# WIFI_BLE.net
KiCad netlist of a schematic drawn in Altium Designer
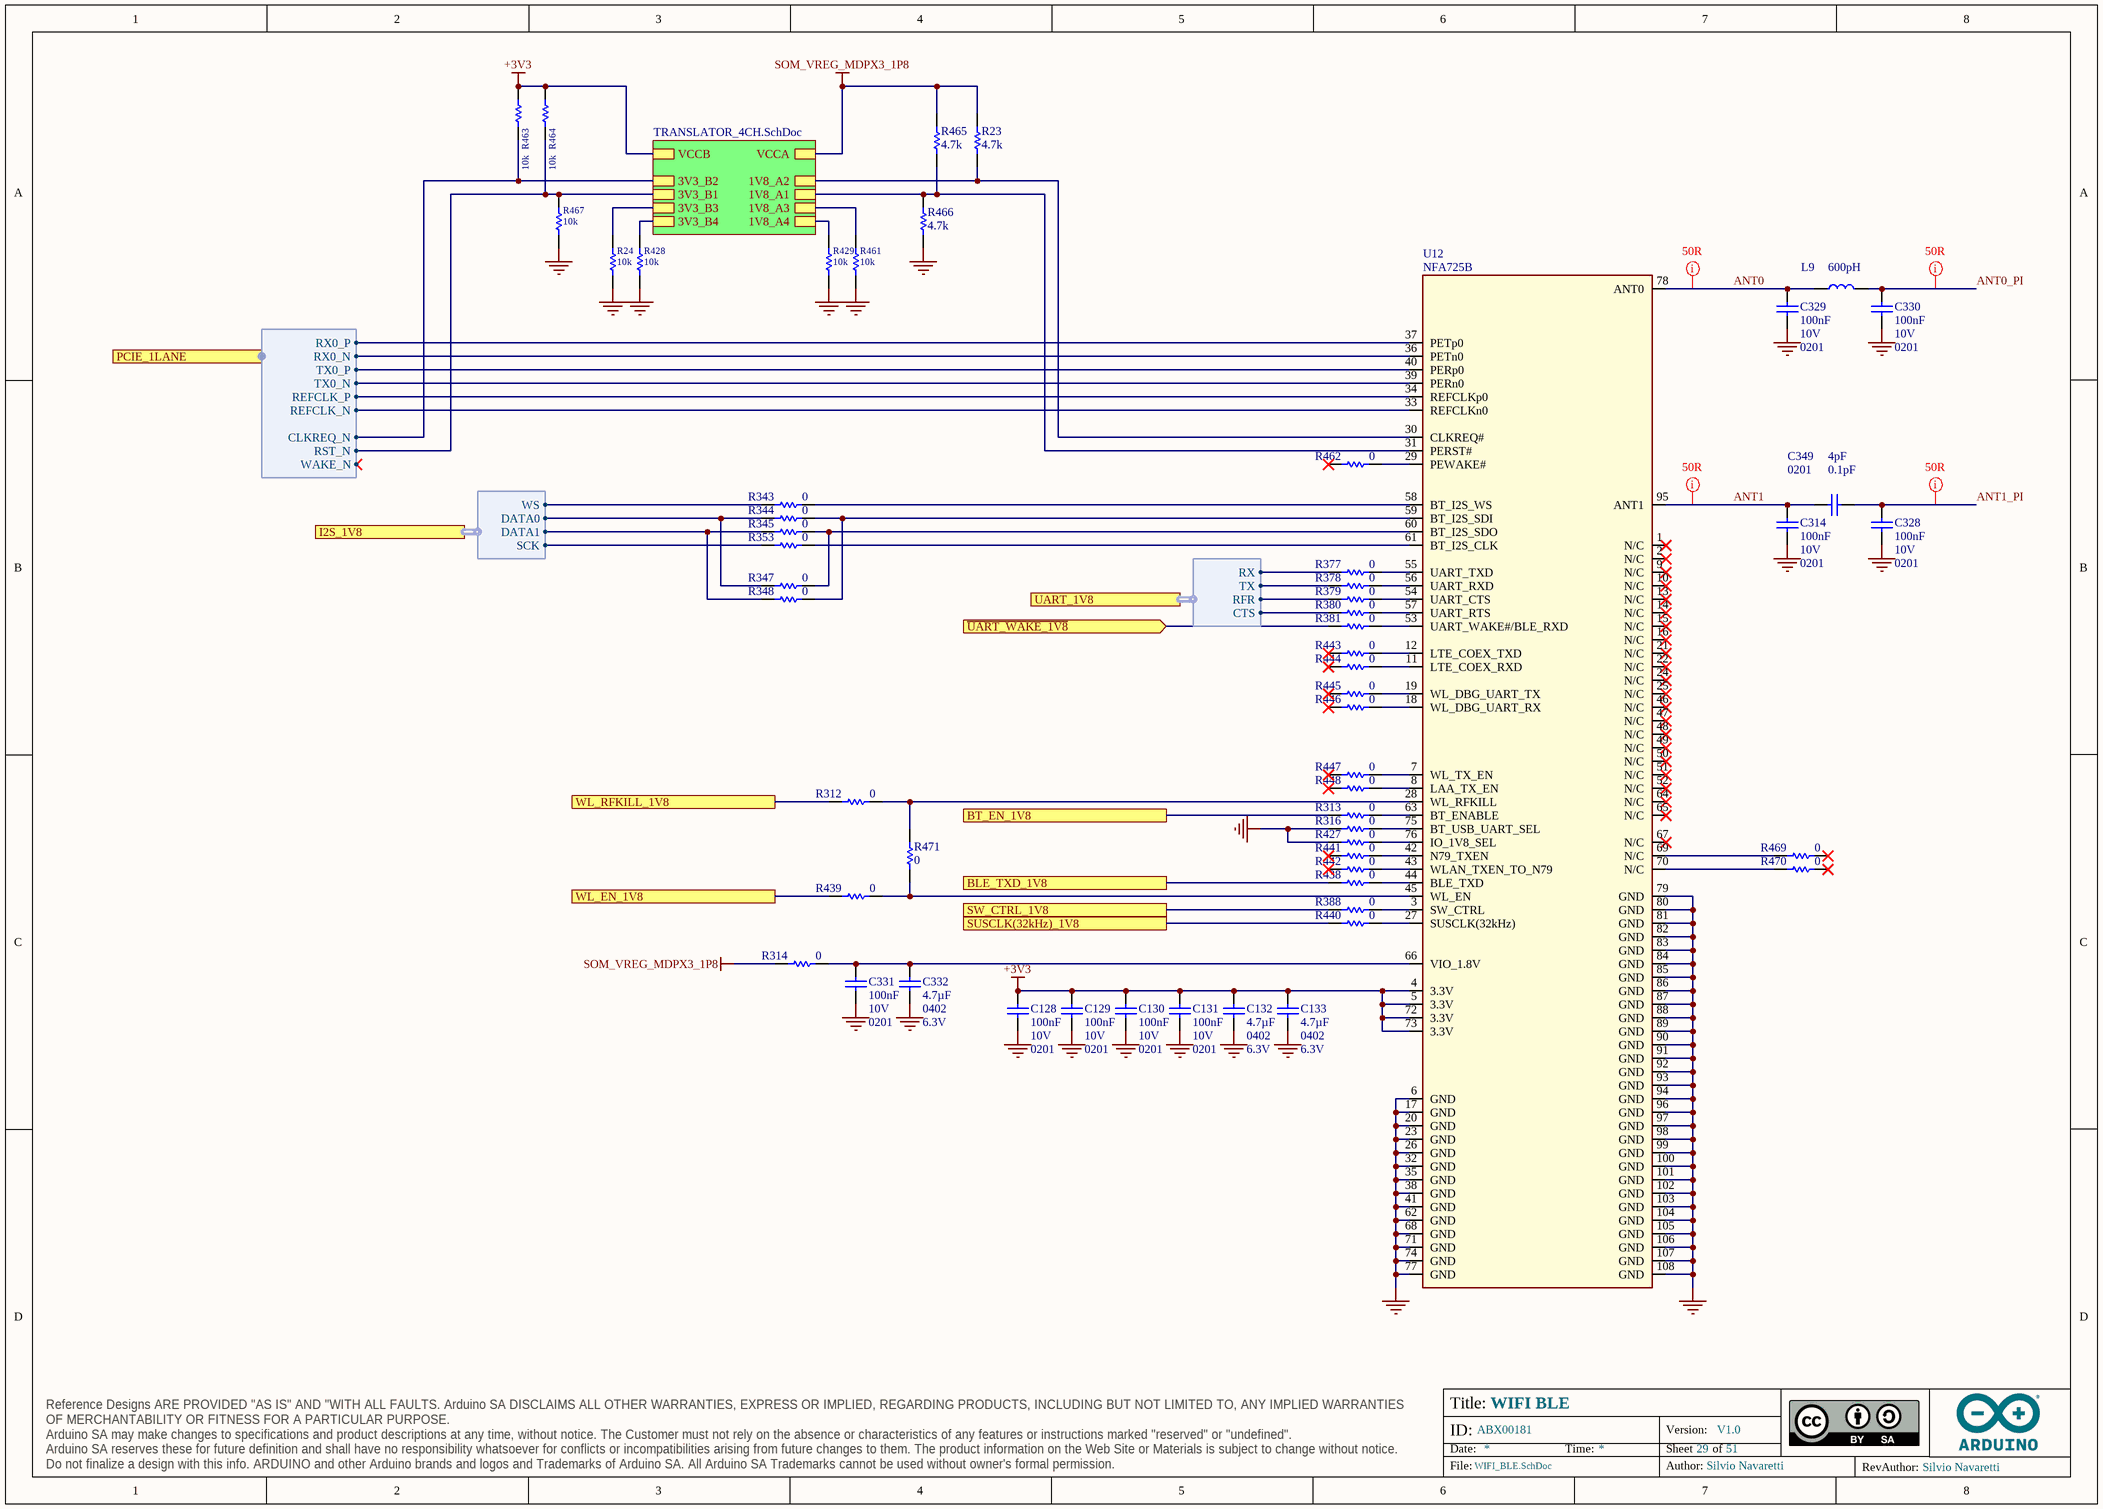
[diagram p0: WIFI_BLE.SchDoc]

(export (version "E")
  (design (tool "Eeschema 10.0.6"))
  (components
    (comp (ref "C128")
      (value "100nF")
      (footprint "CAP-0201")
      (description "CAP CHIP 0201 100nF 10% 10V X5R")
      (fields
        (field (name "PART NUMBER") "CL03A104KP3NNNC")
        (field (name "MANUFACTURER") "Samsung Electro-Mechanics")
        (field (name "VOLTAGE") "10V")
        (field (name "CASE CODE (IMPERIAL)") "0201")
      )
      (libsource (lib "Clean") (part "CAP"))
    )
    (comp (ref "C129")
      (value "100nF")
      (footprint "CAP-0201")
      (description "CAP CHIP 0201 100nF 10% 10V X5R")
      (fields
        (field (name "PART NUMBER") "CL03A104KP3NNNC")
        (field (name "MANUFACTURER") "Samsung Electro-Mechanics")
        (field (name "VOLTAGE") "10V")
        (field (name "CASE CODE (IMPERIAL)") "0201")
      )
      (libsource (lib "Clean") (part "CAP"))
    )
    (comp (ref "C130")
      (value "100nF")
      (footprint "CAP-0201")
      (description "CAP CHIP 0201 100nF 10% 10V X5R")
      (fields
        (field (name "PART NUMBER") "CL03A104KP3NNNC")
        (field (name "MANUFACTURER") "Samsung Electro-Mechanics")
        (field (name "VOLTAGE") "10V")
        (field (name "CASE CODE (IMPERIAL)") "0201")
      )
      (libsource (lib "Clean") (part "CAP"))
    )
    (comp (ref "C131")
      (value "100nF")
      (footprint "CAP-0201")
      (description "CAP CHIP 0201 100nF 10% 10V X5R")
      (fields
        (field (name "PART NUMBER") "CL03A104KP3NNNC")
        (field (name "MANUFACTURER") "Samsung Electro-Mechanics")
        (field (name "VOLTAGE") "10V")
        (field (name "CASE CODE (IMPERIAL)") "0201")
      )
      (libsource (lib "Clean") (part "CAP"))
    )
    (comp (ref "C132")
      (value "4.7µF")
      (footprint "CAP-0402")
      (description "CAP CHIP 0402 4.7uF 20% 6V3 X5R")
      (fields
        (field (name "MANUFACTURER") "Hottech")
        (field (name "PART NUMBER") "C1005A475M6R3NT")
        (field (name "CASE CODE (IMPERIAL)") "0402")
        (field (name "VOLTAGE") "6.3V")
      )
      (libsource (lib "Clean") (part "CAP"))
    )
    (comp (ref "C133")
      (value "4.7µF")
      (footprint "CAP-0402")
      (description "CAP CHIP 0402 4.7uF 20% 6V3 X5R")
      (fields
        (field (name "MANUFACTURER") "Hottech")
        (field (name "PART NUMBER") "C1005A475M6R3NT")
        (field (name "CASE CODE (IMPERIAL)") "0402")
        (field (name "VOLTAGE") "6.3V")
      )
      (libsource (lib "Clean") (part "CAP"))
    )
    (comp (ref "C314")
      (value "100nF")
      (footprint "CAP-0201")
      (description "CAP CHIP 0201 100nF 10% 10V X5R")
      (fields
        (field (name "PART NUMBER") "CL03A104KP3NNNC")
        (field (name "MANUFACTURER") "Samsung Electro-Mechanics")
        (field (name "VOLTAGE") "10V")
        (field (name "CASE CODE (IMPERIAL)") "0201")
      )
      (libsource (lib "Clean") (part "CAP"))
    )
    (comp (ref "C328")
      (value "100nF")
      (footprint "CAP-0201")
      (description "CAP CHIP 0201 100nF 10% 10V X5R")
      (fields
        (field (name "PART NUMBER") "CL03A104KP3NNNC")
        (field (name "MANUFACTURER") "Samsung Electro-Mechanics")
        (field (name "VOLTAGE") "10V")
        (field (name "CASE CODE (IMPERIAL)") "0201")
      )
      (libsource (lib "Clean") (part "CAP"))
    )
    (comp (ref "C329")
      (value "100nF")
      (footprint "CAP-0201")
      (description "CAP CHIP 0201 100nF 10% 10V X5R")
      (fields
        (field (name "PART NUMBER") "CL03A104KP3NNNC")
        (field (name "MANUFACTURER") "Samsung Electro-Mechanics")
        (field (name "VOLTAGE") "10V")
        (field (name "CASE CODE (IMPERIAL)") "0201")
      )
      (libsource (lib "Clean") (part "CAP"))
    )
    (comp (ref "C330")
      (value "100nF")
      (footprint "CAP-0201")
      (description "CAP CHIP 0201 100nF 10% 10V X5R")
      (fields
        (field (name "PART NUMBER") "CL03A104KP3NNNC")
        (field (name "MANUFACTURER") "Samsung Electro-Mechanics")
        (field (name "VOLTAGE") "10V")
        (field (name "CASE CODE (IMPERIAL)") "0201")
      )
      (libsource (lib "Clean") (part "CAP"))
    )
    (comp (ref "C331")
      (value "100nF")
      (footprint "CAP-0201")
      (description "CAP CHIP 0201 100nF 10% 10V X5R")
      (fields
        (field (name "PART NUMBER") "CL03A104KP3NNNC")
        (field (name "MANUFACTURER") "Samsung Electro-Mechanics")
        (field (name "VOLTAGE") "10V")
        (field (name "CASE CODE (IMPERIAL)") "0201")
      )
      (libsource (lib "Clean") (part "CAP"))
    )
    (comp (ref "C332")
      (value "4.7µF")
      (footprint "CAP-0402")
      (description "CAP CHIP 0402 4.7uF 20% 6V3 X5R")
      (fields
        (field (name "MANUFACTURER") "Hottech")
        (field (name "PART NUMBER") "C1005A475M6R3NT")
        (field (name "CASE CODE (IMPERIAL)") "0402")
        (field (name "VOLTAGE") "6.3V")
      )
      (libsource (lib "Clean") (part "CAP"))
    )
    (comp (ref "C349")
      (value "4pF")
      (footprint "CAP-0201")
      (description "CAP CHIP 0201 4pF 0.1pF 50V C0G")
      (fields
        (field (name "MANUFACTURER") "Murata")
        (field (name "CASE CODE (IMPERIAL)") "0201")
        (field (name "PART NUMBER") "GRM0335C1H4R0BA01D")
        (field (name "TOLERANCE") "0.1pF")
      )
      (libsource (lib "Clean") (part "CAP"))
    )
    (comp (ref "L9")
      (value "0201DS-0N6XKEW")
      (footprint "0201DS Coilcraft")
      (description "IND 0201 0.6nH 1A 30mR")
      (fields (field (name "INDUCTANCE") "600pH"))
      (libsource (lib "Clean") (part "Inductor"))
    )
    (comp (ref "R23")
      (value "4.7k")
      (footprint "RES-0201")
      (description "RES CHIP 0201 4k7 1% 1/20W")
      (fields (field (name "POWER") "50mW") (field (name "TOLERANCE") "1%"))
      (libsource (lib "Clean") (part "RES"))
    )
    (comp (ref "R24")
      (value "10k")
      (footprint "RES-0201")
      (description "RES CHIP 0201 10k 1% 1/20W")
      (fields (field (name "POWER") "50mW") (field (name "TOLERANCE") "1%"))
      (libsource (lib "Clean") (part "RES"))
    )
    (comp (ref "R312")
      (value "0")
      (footprint "RES-0201")
      (description "RES CHIP 0201 0R")
      (fields (field (name "MANUFACTURER") "Vishay") (field (name "PART NUMBER") "CRCW02010000Z0ED"))
      (libsource (lib "Clean") (part "RES"))
    )
    (comp (ref "R313")
      (value "0")
      (footprint "RES-0201")
      (description "RES CHIP 0201 0R")
      (fields (field (name "MANUFACTURER") "Vishay") (field (name "PART NUMBER") "CRCW02010000Z0ED"))
      (libsource (lib "Clean") (part "RES"))
    )
    (comp (ref "R314")
      (value "0")
      (footprint "RES-0201")
      (description "RES CHIP 0201 0R")
      (fields (field (name "MANUFACTURER") "Vishay") (field (name "PART NUMBER") "CRCW02010000Z0ED"))
      (libsource (lib "Clean") (part "RES"))
    )
    (comp (ref "R316")
      (value "0")
      (footprint "RES-0201")
      (description "RES CHIP 0201 0R")
      (fields (field (name "MANUFACTURER") "Vishay") (field (name "PART NUMBER") "CRCW02010000Z0ED"))
      (libsource (lib "Clean") (part "RES"))
    )
    (comp (ref "R343")
      (value "0")
      (footprint "RES-0201")
      (description "RES CHIP 0201 0R")
      (fields (field (name "MANUFACTURER") "Vishay") (field (name "PART NUMBER") "CRCW02010000Z0ED"))
      (libsource (lib "Clean") (part "RES"))
    )
    (comp (ref "R344")
      (value "0")
      (footprint "RES-0201")
      (description "RES CHIP 0201 0R")
      (fields (field (name "MANUFACTURER") "Vishay") (field (name "PART NUMBER") "CRCW02010000Z0ED"))
      (libsource (lib "Clean") (part "RES"))
    )
    (comp (ref "R345")
      (value "0")
      (footprint "RES-0201")
      (description "RES CHIP 0201 0R")
      (fields (field (name "MANUFACTURER") "Vishay") (field (name "PART NUMBER") "CRCW02010000Z0ED"))
      (libsource (lib "Clean") (part "RES"))
    )
    (comp (ref "R347")
      (value "0")
      (footprint "RES-0201")
      (description "RES CHIP 0201 0R")
      (fields (field (name "MANUFACTURER") "Vishay") (field (name "PART NUMBER") "CRCW02010000Z0ED"))
      (libsource (lib "Clean") (part "RES"))
    )
    (comp (ref "R348")
      (value "0")
      (footprint "RES-0201")
      (description "RES CHIP 0201 0R")
      (fields (field (name "MANUFACTURER") "Vishay") (field (name "PART NUMBER") "CRCW02010000Z0ED"))
      (libsource (lib "Clean") (part "RES"))
    )
    (comp (ref "R353")
      (value "0")
      (footprint "RES-0201")
      (description "RES CHIP 0201 0R")
      (fields (field (name "MANUFACTURER") "Vishay") (field (name "PART NUMBER") "CRCW02010000Z0ED"))
      (libsource (lib "Clean") (part "RES"))
    )
    (comp (ref "R377")
      (value "0")
      (footprint "RES-0201")
      (description "RES CHIP 0201 0R")
      (fields (field (name "MANUFACTURER") "Vishay") (field (name "PART NUMBER") "CRCW02010000Z0ED"))
      (libsource (lib "Clean") (part "RES"))
    )
    (comp (ref "R378")
      (value "0")
      (footprint "RES-0201")
      (description "RES CHIP 0201 0R")
      (fields (field (name "MANUFACTURER") "Vishay") (field (name "PART NUMBER") "CRCW02010000Z0ED"))
      (libsource (lib "Clean") (part "RES"))
    )
    (comp (ref "R379")
      (value "0")
      (footprint "RES-0201")
      (description "RES CHIP 0201 0R")
      (fields (field (name "MANUFACTURER") "Vishay") (field (name "PART NUMBER") "CRCW02010000Z0ED"))
      (libsource (lib "Clean") (part "RES"))
    )
    (comp (ref "R380")
      (value "0")
      (footprint "RES-0201")
      (description "RES CHIP 0201 0R")
      (fields (field (name "MANUFACTURER") "Vishay") (field (name "PART NUMBER") "CRCW02010000Z0ED"))
      (libsource (lib "Clean") (part "RES"))
    )
    (comp (ref "R381")
      (value "0")
      (footprint "RES-0201")
      (description "RES CHIP 0201 0R")
      (fields (field (name "MANUFACTURER") "Vishay") (field (name "PART NUMBER") "CRCW02010000Z0ED"))
      (libsource (lib "Clean") (part "RES"))
    )
    (comp (ref "R388")
      (value "0")
      (footprint "RES-0201")
      (description "RES CHIP 0201 0R")
      (fields (field (name "MANUFACTURER") "Vishay") (field (name "PART NUMBER") "CRCW02010000Z0ED"))
      (libsource (lib "Clean") (part "RES"))
    )
    (comp (ref "R427")
      (value "0")
      (footprint "RES-0201")
      (description "RES CHIP 0201 0R")
      (fields (field (name "MANUFACTURER") "Vishay") (field (name "PART NUMBER") "CRCW02010000Z0ED"))
      (libsource (lib "Clean") (part "RES"))
    )
    (comp (ref "R428")
      (value "10k")
      (footprint "RES-0201")
      (description "RES CHIP 0201 10k 1% 1/20W")
      (fields (field (name "POWER") "50mW") (field (name "TOLERANCE") "1%"))
      (libsource (lib "Clean") (part "RES"))
    )
    (comp (ref "R429")
      (value "10k")
      (footprint "RES-0201")
      (description "RES CHIP 0201 10k 1% 1/20W")
      (fields (field (name "POWER") "50mW") (field (name "TOLERANCE") "1%"))
      (libsource (lib "Clean") (part "RES"))
    )
    (comp (ref "R438")
      (value "0")
      (footprint "RES-0201")
      (description "RES CHIP 0201 0R")
      (fields (field (name "MANUFACTURER") "Vishay") (field (name "PART NUMBER") "CRCW02010000Z0ED"))
      (libsource (lib "Clean") (part "RES"))
    )
    (comp (ref "R439")
      (value "0")
      (footprint "RES-0201")
      (description "RES CHIP 0201 0R")
      (fields (field (name "MANUFACTURER") "Vishay") (field (name "PART NUMBER") "CRCW02010000Z0ED"))
      (libsource (lib "Clean") (part "RES"))
    )
    (comp (ref "R440")
      (value "0")
      (footprint "RES-0201")
      (description "RES CHIP 0201 0R")
      (fields (field (name "MANUFACTURER") "Vishay") (field (name "PART NUMBER") "CRCW02010000Z0ED"))
      (libsource (lib "Clean") (part "RES"))
    )
    (comp (ref "R441")
      (value "0")
      (footprint "RES-0201")
      (description "RES CHIP 0201 0R")
      (fields (field (name "MANUFACTURER") "Vishay") (field (name "PART NUMBER") "CRCW02010000Z0ED"))
      (libsource (lib "Clean") (part "RES"))
    )
    (comp (ref "R442")
      (value "0")
      (footprint "RES-0201")
      (description "RES CHIP 0201 0R")
      (fields (field (name "MANUFACTURER") "Vishay") (field (name "PART NUMBER") "CRCW02010000Z0ED"))
      (libsource (lib "Clean") (part "RES"))
    )
    (comp (ref "R443")
      (value "0")
      (footprint "RES-0201")
      (description "RES CHIP 0201 0R")
      (fields (field (name "MANUFACTURER") "Vishay") (field (name "PART NUMBER") "CRCW02010000Z0ED"))
      (libsource (lib "Clean") (part "RES"))
    )
    (comp (ref "R444")
      (value "0")
      (footprint "RES-0201")
      (description "RES CHIP 0201 0R")
      (fields (field (name "MANUFACTURER") "Vishay") (field (name "PART NUMBER") "CRCW02010000Z0ED"))
      (libsource (lib "Clean") (part "RES"))
    )
    (comp (ref "R445")
      (value "0")
      (footprint "RES-0201")
      (description "RES CHIP 0201 0R")
      (fields (field (name "MANUFACTURER") "Vishay") (field (name "PART NUMBER") "CRCW02010000Z0ED"))
      (libsource (lib "Clean") (part "RES"))
    )
    (comp (ref "R446")
      (value "0")
      (footprint "RES-0201")
      (description "RES CHIP 0201 0R")
      (fields (field (name "MANUFACTURER") "Vishay") (field (name "PART NUMBER") "CRCW02010000Z0ED"))
      (libsource (lib "Clean") (part "RES"))
    )
    (comp (ref "R447")
      (value "0")
      (footprint "RES-0201")
      (description "RES CHIP 0201 0R")
      (fields (field (name "MANUFACTURER") "Vishay") (field (name "PART NUMBER") "CRCW02010000Z0ED"))
      (libsource (lib "Clean") (part "RES"))
    )
    (comp (ref "R448")
      (value "0")
      (footprint "RES-0201")
      (description "RES CHIP 0201 0R")
      (fields (field (name "MANUFACTURER") "Vishay") (field (name "PART NUMBER") "CRCW02010000Z0ED"))
      (libsource (lib "Clean") (part "RES"))
    )
    (comp (ref "R461")
      (value "10k")
      (footprint "RES-0201")
      (description "RES CHIP 0201 10k 1% 1/20W")
      (fields (field (name "POWER") "50mW") (field (name "TOLERANCE") "1%"))
      (libsource (lib "Clean") (part "RES"))
    )
    (comp (ref "R462")
      (value "0")
      (footprint "RES-0201")
      (description "RES CHIP 0201 0R")
      (fields (field (name "MANUFACTURER") "Vishay") (field (name "PART NUMBER") "CRCW02010000Z0ED"))
      (libsource (lib "Clean") (part "RES"))
    )
    (comp (ref "R463")
      (value "10k")
      (footprint "RES-0201")
      (description "RES CHIP 0201 10k 1% 1/20W")
      (fields (field (name "POWER") "50mW") (field (name "TOLERANCE") "1%"))
      (libsource (lib "Clean") (part "RES"))
    )
    (comp (ref "R464")
      (value "10k")
      (footprint "RES-0201")
      (description "RES CHIP 0201 10k 1% 1/20W")
      (fields (field (name "POWER") "50mW") (field (name "TOLERANCE") "1%"))
      (libsource (lib "Clean") (part "RES"))
    )
    (comp (ref "R465")
      (value "4.7k")
      (footprint "RES-0201")
      (description "RES CHIP 0201 4k7 1% 1/20W")
      (fields (field (name "POWER") "50mW") (field (name "TOLERANCE") "1%"))
      (libsource (lib "Clean") (part "RES"))
    )
    (comp (ref "R466")
      (value "4.7k")
      (footprint "RES-0201")
      (description "RES CHIP 0201 4k7 1% 1/20W")
      (fields (field (name "POWER") "50mW") (field (name "TOLERANCE") "1%"))
      (libsource (lib "Clean") (part "RES"))
    )
    (comp (ref "R467")
      (value "10k")
      (footprint "RES-0201")
      (description "RES CHIP 0201 10k 1% 1/20W")
      (fields (field (name "POWER") "50mW") (field (name "TOLERANCE") "1%"))
      (libsource (lib "Clean") (part "RES"))
    )
    (comp (ref "R469")
      (value "0")
      (footprint "RES-0201")
      (description "RES CHIP 0201 0R")
      (fields (field (name "MANUFACTURER") "Vishay") (field (name "PART NUMBER") "CRCW02010000Z0ED"))
      (libsource (lib "Clean") (part "RES"))
    )
    (comp (ref "R470")
      (value "0")
      (footprint "RES-0201")
      (description "RES CHIP 0201 0R")
      (fields (field (name "MANUFACTURER") "Vishay") (field (name "PART NUMBER") "CRCW02010000Z0ED"))
      (libsource (lib "Clean") (part "RES"))
    )
    (comp (ref "R471")
      (value "0")
      (footprint "RES-0201")
      (description "RES CHIP 0201 0R")
      (fields (field (name "MANUFACTURER") "Vishay") (field (name "PART NUMBER") "CRCW02010000Z0ED"))
      (libsource (lib "Clean") (part "RES"))
    )
    (comp (ref "U12")
      (value "NFA725B")
      (footprint "NFA725B")
      (description "Module 802.11a/b/g/n/ac/ax 2x2 MAC + BT 5.2, QCA2066, with 2 antenna pads, PCIe, LGA76 14x17.68mm")
      (fields (field (name "MANUFACTURER") "USI"))
      (libsource (lib "Clean") (part "NFA725B"))
    )
  )
  (nets
    (net (code "4") (name "+3V3") (class "Default")
      (node (ref "C128") (pin "2") (pinfunction "2_2") (pintype "passive"))
      (node (ref "C129") (pin "2") (pinfunction "2_2") (pintype "passive"))
      (node (ref "C130") (pin "2") (pinfunction "2_2") (pintype "passive"))
      (node (ref "C131") (pin "2") (pinfunction "2_2") (pintype "passive"))
      (node (ref "C132") (pin "1") (pinfunction "1_1") (pintype "passive"))
      (node (ref "C133") (pin "1") (pinfunction "1_1") (pintype "passive"))
      (node (ref "R463") (pin "1") (pinfunction "1_1") (pintype "passive"))
      (node (ref "R464") (pin "1") (pinfunction "1_1") (pintype "passive"))
      (node (ref "U12") (pin "4") (pinfunction "3.3V_4") (pintype "passive"))
      (node (ref "U12") (pin "5") (pinfunction "3.3V_5") (pintype "passive"))
      (node (ref "U12") (pin "72") (pinfunction "3.3V_72") (pintype "passive"))
      (node (ref "U12") (pin "73") (pinfunction "3.3V_73") (pintype "passive"))
    )
    (net (code "5") (name "/1V8_A1") (class "Default")
      (node (ref "R465") (pin "1") (pinfunction "1_1") (pintype "passive"))
      (node (ref "R466") (pin "2") (pinfunction "2_2") (pintype "passive"))
      (node (ref "U12") (pin "31") (pinfunction "PERST#_31") (pintype "passive"))
    )
    (net (code "6") (name "/1V8_A2") (class "Default")
      (node (ref "R23") (pin "1") (pinfunction "1_1") (pintype "passive"))
      (node (ref "U12") (pin "30") (pinfunction "CLKREQ#_30") (pintype "passive"))
    )
    (net (code "7") (name "/1V8_A3") (class "Default")
      (node (ref "R461") (pin "2") (pinfunction "2_2") (pintype "passive"))
    )
    (net (code "8") (name "/1V8_A4") (class "Default")
      (node (ref "R429") (pin "2") (pinfunction "2_2") (pintype "passive"))
    )
    (net (code "9") (name "/3V3_B1") (class "Default")
      (node (ref "R464") (pin "2") (pinfunction "2_2") (pintype "passive"))
      (node (ref "R467") (pin "2") (pinfunction "2_2") (pintype "passive"))
    )
    (net (code "10") (name "/3V3_B2") (class "Default")
      (node (ref "R463") (pin "2") (pinfunction "2_2") (pintype "passive"))
    )
    (net (code "11") (name "/3V3_B3") (class "Default")
      (node (ref "R24") (pin "2") (pinfunction "2_2") (pintype "passive"))
    )
    (net (code "12") (name "/3V3_B4") (class "Default")
      (node (ref "R428") (pin "2") (pinfunction "2_2") (pintype "passive"))
    )
    (net (code "13") (name "/ANT0") (class "Default")
      (node (ref "C329") (pin "2") (pinfunction "2_2") (pintype "passive"))
      (node (ref "L9") (pin "1") (pinfunction "1_1") (pintype "passive"))
      (node (ref "U12") (pin "78") (pinfunction "ANT0_78") (pintype "passive"))
    )
    (net (code "14") (name "/ANT0_PI") (class "Default")
      (node (ref "C330") (pin "2") (pinfunction "2_2") (pintype "passive"))
      (node (ref "L9") (pin "2") (pinfunction "2_2") (pintype "passive"))
    )
    (net (code "15") (name "/ANT1") (class "Default")
      (node (ref "C314") (pin "2") (pinfunction "2_2") (pintype "passive"))
      (node (ref "C349") (pin "2") (pinfunction "2_2") (pintype "passive"))
      (node (ref "U12") (pin "95") (pinfunction "ANT1_95") (pintype "passive"))
    )
    (net (code "16") (name "/ANT1_PI") (class "Default")
      (node (ref "C328") (pin "2") (pinfunction "2_2") (pintype "passive"))
      (node (ref "C349") (pin "1") (pinfunction "1_1") (pintype "passive"))
    )
    (net (code "17") (name "/BLE_TXD_1V8") (class "Default")
      (node (ref "R438") (pin "1") (pinfunction "1_1") (pintype "passive"))
    )
    (net (code "18") (name "/BT_EN_1V8") (class "Default")
      (node (ref "R313") (pin "1") (pinfunction "1_1") (pintype "passive"))
    )
    (net (code "19") (name "/SUSCLK(32kHz)_1V8") (class "Default")
      (node (ref "R440") (pin "1") (pinfunction "1_1") (pintype "passive"))
    )
    (net (code "20") (name "/SW_CTRL_1V8") (class "Default")
      (node (ref "R388") (pin "1") (pinfunction "1_1") (pintype "passive"))
    )
    (net (code "21") (name "/WL_EN_1V8") (class "Default")
      (node (ref "R439") (pin "1") (pinfunction "1_1") (pintype "passive"))
    )
    (net (code "22") (name "/WL_RFKILL_1V8") (class "Default")
      (node (ref "R312") (pin "1") (pinfunction "1_1") (pintype "passive"))
    )
    (net (code "26") (name "/~{UART_WAKE_1V8}") (class "Default")
      (node (ref "R381") (pin "1") (pinfunction "1_1") (pintype "passive"))
    )
    (net (code "27") (name "GND") (class "Default")
      (node (ref "C128") (pin "1") (pinfunction "1_1") (pintype "passive"))
      (node (ref "C129") (pin "1") (pinfunction "1_1") (pintype "passive"))
      (node (ref "C130") (pin "1") (pinfunction "1_1") (pintype "passive"))
      (node (ref "C131") (pin "1") (pinfunction "1_1") (pintype "passive"))
      (node (ref "C132") (pin "2") (pinfunction "2_2") (pintype "passive"))
      (node (ref "C133") (pin "2") (pinfunction "2_2") (pintype "passive"))
      (node (ref "C314") (pin "1") (pinfunction "1_1") (pintype "passive"))
      (node (ref "C328") (pin "1") (pinfunction "1_1") (pintype "passive"))
      (node (ref "C329") (pin "1") (pinfunction "1_1") (pintype "passive"))
      (node (ref "C330") (pin "1") (pinfunction "1_1") (pintype "passive"))
      (node (ref "C331") (pin "1") (pinfunction "1_1") (pintype "passive"))
      (node (ref "C332") (pin "2") (pinfunction "2_2") (pintype "passive"))
      (node (ref "R24") (pin "1") (pinfunction "1_1") (pintype "passive"))
      (node (ref "R316") (pin "1") (pinfunction "1_1") (pintype "passive"))
      (node (ref "R427") (pin "1") (pinfunction "1_1") (pintype "passive"))
      (node (ref "R428") (pin "1") (pinfunction "1_1") (pintype "passive"))
      (node (ref "R429") (pin "1") (pinfunction "1_1") (pintype "passive"))
      (node (ref "R461") (pin "1") (pinfunction "1_1") (pintype "passive"))
      (node (ref "R466") (pin "1") (pinfunction "1_1") (pintype "passive"))
      (node (ref "R467") (pin "1") (pinfunction "1_1") (pintype "passive"))
      (node (ref "U12") (pin "100") (pinfunction "GND_100") (pintype "passive"))
      (node (ref "U12") (pin "101") (pinfunction "GND_101") (pintype "passive"))
      (node (ref "U12") (pin "102") (pinfunction "GND_102") (pintype "passive"))
      (node (ref "U12") (pin "103") (pinfunction "GND_103") (pintype "passive"))
      (node (ref "U12") (pin "104") (pinfunction "GND_104") (pintype "passive"))
      (node (ref "U12") (pin "105") (pinfunction "GND_105") (pintype "passive"))
      (node (ref "U12") (pin "106") (pinfunction "GND_106") (pintype "passive"))
      (node (ref "U12") (pin "107") (pinfunction "GND_107") (pintype "passive"))
      (node (ref "U12") (pin "108") (pinfunction "GND_108") (pintype "passive"))
      (node (ref "U12") (pin "17") (pinfunction "GND_17") (pintype "passive"))
      (node (ref "U12") (pin "20") (pinfunction "GND_20") (pintype "passive"))
      (node (ref "U12") (pin "23") (pinfunction "GND_23") (pintype "passive"))
      (node (ref "U12") (pin "26") (pinfunction "GND_26") (pintype "passive"))
      (node (ref "U12") (pin "32") (pinfunction "GND_32") (pintype "passive"))
      (node (ref "U12") (pin "35") (pinfunction "GND_35") (pintype "passive"))
      (node (ref "U12") (pin "38") (pinfunction "GND_38") (pintype "passive"))
      (node (ref "U12") (pin "41") (pinfunction "GND_41") (pintype "passive"))
      (node (ref "U12") (pin "6") (pinfunction "GND_6") (pintype "passive"))
      (node (ref "U12") (pin "62") (pinfunction "GND_62") (pintype "passive"))
      (node (ref "U12") (pin "68") (pinfunction "GND_68") (pintype "passive"))
      (node (ref "U12") (pin "71") (pinfunction "GND_71") (pintype "passive"))
      (node (ref "U12") (pin "74") (pinfunction "GND_74") (pintype "passive"))
      (node (ref "U12") (pin "77") (pinfunction "GND_77") (pintype "passive"))
      (node (ref "U12") (pin "79") (pinfunction "GND_79") (pintype "passive"))
      (node (ref "U12") (pin "80") (pinfunction "GND_80") (pintype "passive"))
      (node (ref "U12") (pin "81") (pinfunction "GND_81") (pintype "passive"))
      (node (ref "U12") (pin "82") (pinfunction "GND_82") (pintype "passive"))
      (node (ref "U12") (pin "83") (pinfunction "GND_83") (pintype "passive"))
      (node (ref "U12") (pin "84") (pinfunction "GND_84") (pintype "passive"))
      (node (ref "U12") (pin "85") (pinfunction "GND_85") (pintype "passive"))
      (node (ref "U12") (pin "86") (pinfunction "GND_86") (pintype "passive"))
      (node (ref "U12") (pin "87") (pinfunction "GND_87") (pintype "passive"))
      (node (ref "U12") (pin "88") (pinfunction "GND_88") (pintype "passive"))
      (node (ref "U12") (pin "89") (pinfunction "GND_89") (pintype "passive"))
      (node (ref "U12") (pin "90") (pinfunction "GND_90") (pintype "passive"))
      (node (ref "U12") (pin "91") (pinfunction "GND_91") (pintype "passive"))
      (node (ref "U12") (pin "92") (pinfunction "GND_92") (pintype "passive"))
      (node (ref "U12") (pin "93") (pinfunction "GND_93") (pintype "passive"))
      (node (ref "U12") (pin "94") (pinfunction "GND_94") (pintype "passive"))
      (node (ref "U12") (pin "96") (pinfunction "GND_96") (pintype "passive"))
      (node (ref "U12") (pin "97") (pinfunction "GND_97") (pintype "passive"))
      (node (ref "U12") (pin "98") (pinfunction "GND_98") (pintype "passive"))
      (node (ref "U12") (pin "99") (pinfunction "GND_99") (pintype "passive"))
    )
    (net (code "28") (name "Net-(R344-Pad1)") (class "Default")
      (node (ref "R344") (pin "1") (pinfunction "1_1") (pintype "passive"))
      (node (ref "R347") (pin "1") (pinfunction "1_1") (pintype "passive"))
    )
    (net (code "29") (name "Net-(R345-Pad1)") (class "Default")
      (node (ref "R345") (pin "1") (pinfunction "1_1") (pintype "passive"))
      (node (ref "R348") (pin "1") (pinfunction "1_1") (pintype "passive"))
    )
    (net (code "30") (name "Net-(R469-Pad1)") (class "Default")
      (node (ref "R469") (pin "1") (pinfunction "1_1") (pintype "passive"))
      (node (ref "U12") (pin "69") (pinfunction "N/C_69") (pintype "passive"))
    )
    (net (code "31") (name "Net-(R470-Pad1)") (class "Default")
      (node (ref "R470") (pin "1") (pinfunction "1_1") (pintype "passive"))
      (node (ref "U12") (pin "70") (pinfunction "N/C_70") (pintype "passive"))
    )
    (net (code "32") (name "Net-(U12-BLE_TXD)") (class "Default")
      (node (ref "R438") (pin "2") (pinfunction "2_2") (pintype "passive"))
      (node (ref "U12") (pin "44") (pinfunction "BLE_TXD_44") (pintype "passive"))
    )
    (net (code "33") (name "Net-(U12-BT_ENABLE)") (class "Default")
      (node (ref "R313") (pin "2") (pinfunction "2_2") (pintype "passive"))
      (node (ref "U12") (pin "63") (pinfunction "BT_ENABLE_63") (pintype "passive"))
    )
    (net (code "34") (name "Net-(U12-BT_I2S_CLK)") (class "Default")
      (node (ref "R353") (pin "2") (pinfunction "2_2") (pintype "passive"))
      (node (ref "U12") (pin "61") (pinfunction "BT_I2S_CLK_61") (pintype "passive"))
    )
    (net (code "35") (name "Net-(U12-BT_I2S_SDI)") (class "Default")
      (node (ref "R344") (pin "2") (pinfunction "2_2") (pintype "passive"))
      (node (ref "R348") (pin "2") (pinfunction "2_2") (pintype "passive"))
      (node (ref "U12") (pin "59") (pinfunction "BT_I2S_SDI_59") (pintype "passive"))
    )
    (net (code "36") (name "Net-(U12-BT_I2S_SDO)") (class "Default")
      (node (ref "R345") (pin "2") (pinfunction "2_2") (pintype "passive"))
      (node (ref "R347") (pin "2") (pinfunction "2_2") (pintype "passive"))
      (node (ref "U12") (pin "60") (pinfunction "BT_I2S_SDO_60") (pintype "passive"))
    )
    (net (code "37") (name "Net-(U12-BT_I2S_WS)") (class "Default")
      (node (ref "R343") (pin "2") (pinfunction "2_2") (pintype "passive"))
      (node (ref "U12") (pin "58") (pinfunction "BT_I2S_WS_58") (pintype "passive"))
    )
    (net (code "38") (name "Net-(U12-BT_USB_UART_SEL)") (class "Default")
      (node (ref "R316") (pin "2") (pinfunction "2_2") (pintype "passive"))
      (node (ref "U12") (pin "75") (pinfunction "BT_USB_UART_SEL_75") (pintype "passive"))
    )
    (net (code "39") (name "Net-(U12-IO_1V8_SEL)") (class "Default")
      (node (ref "R427") (pin "2") (pinfunction "2_2") (pintype "passive"))
      (node (ref "U12") (pin "76") (pinfunction "IO_1V8_SEL_76") (pintype "passive"))
    )
    (net (code "40") (name "Net-(U12-LAA_TX_EN)") (class "Default")
      (node (ref "R448") (pin "2") (pinfunction "2_2") (pintype "passive"))
      (node (ref "U12") (pin "8") (pinfunction "LAA_TX_EN_8") (pintype "passive"))
    )
    (net (code "41") (name "Net-(U12-LTE_COEX_RXD)") (class "Default")
      (node (ref "R444") (pin "2") (pinfunction "2_2") (pintype "passive"))
      (node (ref "U12") (pin "11") (pinfunction "LTE_COEX_RXD_11") (pintype "passive"))
    )
    (net (code "42") (name "Net-(U12-LTE_COEX_TXD)") (class "Default")
      (node (ref "R443") (pin "2") (pinfunction "2_2") (pintype "passive"))
      (node (ref "U12") (pin "12") (pinfunction "LTE_COEX_TXD_12") (pintype "passive"))
    )
    (net (code "43") (name "Net-(U12-N79_TXEN)") (class "Default")
      (node (ref "R441") (pin "2") (pinfunction "2_2") (pintype "passive"))
      (node (ref "U12") (pin "42") (pinfunction "N79_TXEN_42") (pintype "passive"))
    )
    (net (code "44") (name "Net-(U12-PEWAKE#)") (class "Default")
      (node (ref "R462") (pin "2") (pinfunction "2_2") (pintype "passive"))
      (node (ref "U12") (pin "29") (pinfunction "PEWAKE#_29") (pintype "passive"))
    )
    (net (code "45") (name "Net-(U12-SUSCLK(32kHz))") (class "Default")
      (node (ref "R440") (pin "2") (pinfunction "2_2") (pintype "passive"))
      (node (ref "U12") (pin "27") (pinfunction "SUSCLK(32kHz)_27") (pintype "passive"))
    )
    (net (code "46") (name "Net-(U12-SW_CTRL)") (class "Default")
      (node (ref "R388") (pin "2") (pinfunction "2_2") (pintype "passive"))
      (node (ref "U12") (pin "3") (pinfunction "SW_CTRL_3") (pintype "passive"))
    )
    (net (code "47") (name "Net-(U12-UART_CTS)") (class "Default")
      (node (ref "R379") (pin "2") (pinfunction "2_2") (pintype "passive"))
      (node (ref "U12") (pin "54") (pinfunction "UART_CTS_54") (pintype "passive"))
    )
    (net (code "48") (name "Net-(U12-UART_RTS)") (class "Default")
      (node (ref "R380") (pin "2") (pinfunction "2_2") (pintype "passive"))
      (node (ref "U12") (pin "57") (pinfunction "UART_RTS_57") (pintype "passive"))
    )
    (net (code "49") (name "Net-(U12-UART_RXD)") (class "Default")
      (node (ref "R378") (pin "2") (pinfunction "2_2") (pintype "passive"))
      (node (ref "U12") (pin "56") (pinfunction "UART_RXD_56") (pintype "passive"))
    )
    (net (code "50") (name "Net-(U12-UART_TXD)") (class "Default")
      (node (ref "R377") (pin "2") (pinfunction "2_2") (pintype "passive"))
      (node (ref "U12") (pin "55") (pinfunction "UART_TXD_55") (pintype "passive"))
    )
    (net (code "51") (name "Net-(U12-UART_WAKE#{slash}BLE_RXD)") (class "Default")
      (node (ref "R381") (pin "2") (pinfunction "2_2") (pintype "passive"))
      (node (ref "U12") (pin "53") (pinfunction "UART_WAKE#/BLE_RXD_53") (pintype "passive"))
    )
    (net (code "52") (name "Net-(U12-VIO_1.8V)") (class "Default")
      (node (ref "C331") (pin "2") (pinfunction "2_2") (pintype "passive"))
      (node (ref "C332") (pin "1") (pinfunction "1_1") (pintype "passive"))
      (node (ref "R314") (pin "2") (pinfunction "2_2") (pintype "passive"))
      (node (ref "U12") (pin "66") (pinfunction "VIO_1.8V_66") (pintype "passive"))
    )
    (net (code "53") (name "Net-(U12-WLAN_TXEN_TO_N79)") (class "Default")
      (node (ref "R442") (pin "2") (pinfunction "2_2") (pintype "passive"))
      (node (ref "U12") (pin "43") (pinfunction "WLAN_TXEN_TO_N79_43") (pintype "passive"))
    )
    (net (code "54") (name "Net-(U12-WL_DBG_UART_RX)") (class "Default")
      (node (ref "R446") (pin "2") (pinfunction "2_2") (pintype "passive"))
      (node (ref "U12") (pin "18") (pinfunction "WL_DBG_UART_RX_18") (pintype "passive"))
    )
    (net (code "55") (name "Net-(U12-WL_DBG_UART_TX)") (class "Default")
      (node (ref "R445") (pin "2") (pinfunction "2_2") (pintype "passive"))
      (node (ref "U12") (pin "19") (pinfunction "WL_DBG_UART_TX_19") (pintype "passive"))
    )
    (net (code "56") (name "Net-(U12-WL_EN)") (class "Default")
      (node (ref "R439") (pin "2") (pinfunction "2_2") (pintype "passive"))
      (node (ref "R471") (pin "2") (pinfunction "2_2") (pintype "passive"))
      (node (ref "U12") (pin "45") (pinfunction "WL_EN_45") (pintype "passive"))
    )
    (net (code "57") (name "Net-(U12-WL_RFKILL)") (class "Default")
      (node (ref "R312") (pin "2") (pinfunction "2_2") (pintype "passive"))
      (node (ref "R471") (pin "1") (pinfunction "1_1") (pintype "passive"))
      (node (ref "U12") (pin "28") (pinfunction "WL_RFKILL_28") (pintype "passive"))
    )
    (net (code "58") (name "Net-(U12-WL_TX_EN)") (class "Default")
      (node (ref "R447") (pin "2") (pinfunction "2_2") (pintype "passive"))
      (node (ref "U12") (pin "7") (pinfunction "WL_TX_EN_7") (pintype "passive"))
    )
    (net (code "59") (name "SOM_VREG_MDPX3_1P8") (class "Default")
      (node (ref "R23") (pin "2") (pinfunction "2_2") (pintype "passive"))
      (node (ref "R314") (pin "1") (pinfunction "1_1") (pintype "passive"))
      (node (ref "R465") (pin "2") (pinfunction "2_2") (pintype "passive"))
    )
    (net (code "60") (name "unconnected-(R343-Pad1)") (class "Default")
      (node (ref "R343") (pin "1") (pinfunction "1_1") (pintype "passive"))
    )
    (net (code "61") (name "unconnected-(R353-Pad1)") (class "Default")
      (node (ref "R353") (pin "1") (pinfunction "1_1") (pintype "passive"))
    )
    (net (code "62") (name "unconnected-(R377-Pad1)") (class "Default")
      (node (ref "R377") (pin "1") (pinfunction "1_1") (pintype "passive"))
    )
    (net (code "63") (name "unconnected-(R378-Pad1)") (class "Default")
      (node (ref "R378") (pin "1") (pinfunction "1_1") (pintype "passive"))
    )
    (net (code "64") (name "unconnected-(R379-Pad1)") (class "Default")
      (node (ref "R379") (pin "1") (pinfunction "1_1") (pintype "passive"))
    )
    (net (code "65") (name "unconnected-(R380-Pad1)") (class "Default")
      (node (ref "R380") (pin "1") (pinfunction "1_1") (pintype "passive"))
    )
    (net (code "66") (name "unconnected-(R441-Pad1)") (class "Default")
      (node (ref "R441") (pin "1") (pinfunction "1_1") (pintype "passive+no_connect"))
    )
    (net (code "67") (name "unconnected-(R442-Pad1)") (class "Default")
      (node (ref "R442") (pin "1") (pinfunction "1_1") (pintype "passive+no_connect"))
    )
    (net (code "68") (name "unconnected-(R443-Pad1)") (class "Default")
      (node (ref "R443") (pin "1") (pinfunction "1_1") (pintype "passive+no_connect"))
    )
    (net (code "69") (name "unconnected-(R444-Pad1)") (class "Default")
      (node (ref "R444") (pin "1") (pinfunction "1_1") (pintype "passive+no_connect"))
    )
    (net (code "70") (name "unconnected-(R445-Pad1)") (class "Default")
      (node (ref "R445") (pin "1") (pinfunction "1_1") (pintype "passive+no_connect"))
    )
    (net (code "71") (name "unconnected-(R446-Pad1)") (class "Default")
      (node (ref "R446") (pin "1") (pinfunction "1_1") (pintype "passive+no_connect"))
    )
    (net (code "72") (name "unconnected-(R447-Pad1)") (class "Default")
      (node (ref "R447") (pin "1") (pinfunction "1_1") (pintype "passive+no_connect"))
    )
    (net (code "73") (name "unconnected-(R448-Pad1)") (class "Default")
      (node (ref "R448") (pin "1") (pinfunction "1_1") (pintype "passive+no_connect"))
    )
    (net (code "74") (name "unconnected-(R462-Pad1)") (class "Default")
      (node (ref "R462") (pin "1") (pinfunction "1_1") (pintype "passive+no_connect"))
    )
    (net (code "75") (name "unconnected-(R469-Pad2)") (class "Default")
      (node (ref "R469") (pin "2") (pinfunction "2_2") (pintype "passive+no_connect"))
    )
    (net (code "76") (name "unconnected-(R470-Pad2)") (class "Default")
      (node (ref "R470") (pin "2") (pinfunction "2_2") (pintype "passive+no_connect"))
    )
    (net (code "77") (name "unconnected-(U12-N{slash}C-Pad1)") (class "Default")
      (node (ref "U12") (pin "1") (pinfunction "N/C_1") (pintype "passive+no_connect"))
    )
    (net (code "78") (name "unconnected-(U12-N{slash}C-Pad2)") (class "Default")
      (node (ref "U12") (pin "2") (pinfunction "N/C_2") (pintype "passive+no_connect"))
    )
    (net (code "79") (name "unconnected-(U12-N{slash}C-Pad9)") (class "Default")
      (node (ref "U12") (pin "9") (pinfunction "N/C_9") (pintype "passive+no_connect"))
    )
    (net (code "80") (name "unconnected-(U12-N{slash}C-Pad10)") (class "Default")
      (node (ref "U12") (pin "10") (pinfunction "N/C_10") (pintype "passive+no_connect"))
    )
    (net (code "81") (name "unconnected-(U12-N{slash}C-Pad13)") (class "Default")
      (node (ref "U12") (pin "13") (pinfunction "N/C_13") (pintype "passive+no_connect"))
    )
    (net (code "82") (name "unconnected-(U12-N{slash}C-Pad14)") (class "Default")
      (node (ref "U12") (pin "14") (pinfunction "N/C_14") (pintype "passive+no_connect"))
    )
    (net (code "83") (name "unconnected-(U12-N{slash}C-Pad15)") (class "Default")
      (node (ref "U12") (pin "15") (pinfunction "N/C_15") (pintype "passive+no_connect"))
    )
    (net (code "84") (name "unconnected-(U12-N{slash}C-Pad16)") (class "Default")
      (node (ref "U12") (pin "16") (pinfunction "N/C_16") (pintype "passive+no_connect"))
    )
    (net (code "85") (name "unconnected-(U12-N{slash}C-Pad21)") (class "Default")
      (node (ref "U12") (pin "21") (pinfunction "N/C_21") (pintype "passive+no_connect"))
    )
    (net (code "86") (name "unconnected-(U12-N{slash}C-Pad22)") (class "Default")
      (node (ref "U12") (pin "22") (pinfunction "N/C_22") (pintype "passive+no_connect"))
    )
    (net (code "87") (name "unconnected-(U12-N{slash}C-Pad24)") (class "Default")
      (node (ref "U12") (pin "24") (pinfunction "N/C_24") (pintype "passive+no_connect"))
    )
    (net (code "88") (name "unconnected-(U12-N{slash}C-Pad25)") (class "Default")
      (node (ref "U12") (pin "25") (pinfunction "N/C_25") (pintype "passive+no_connect"))
    )
    (net (code "89") (name "unconnected-(U12-N{slash}C-Pad46)") (class "Default")
      (node (ref "U12") (pin "46") (pinfunction "N/C_46") (pintype "passive+no_connect"))
    )
    (net (code "90") (name "unconnected-(U12-N{slash}C-Pad47)") (class "Default")
      (node (ref "U12") (pin "47") (pinfunction "N/C_47") (pintype "passive+no_connect"))
    )
    (net (code "91") (name "unconnected-(U12-N{slash}C-Pad48)") (class "Default")
      (node (ref "U12") (pin "48") (pinfunction "N/C_48") (pintype "passive+no_connect"))
    )
    (net (code "92") (name "unconnected-(U12-N{slash}C-Pad49)") (class "Default")
      (node (ref "U12") (pin "49") (pinfunction "N/C_49") (pintype "passive+no_connect"))
    )
    (net (code "93") (name "unconnected-(U12-N{slash}C-Pad50)") (class "Default")
      (node (ref "U12") (pin "50") (pinfunction "N/C_50") (pintype "passive+no_connect"))
    )
    (net (code "94") (name "unconnected-(U12-N{slash}C-Pad51)") (class "Default")
      (node (ref "U12") (pin "51") (pinfunction "N/C_51") (pintype "passive+no_connect"))
    )
    (net (code "95") (name "unconnected-(U12-N{slash}C-Pad52)") (class "Default")
      (node (ref "U12") (pin "52") (pinfunction "N/C_52") (pintype "passive+no_connect"))
    )
    (net (code "96") (name "unconnected-(U12-N{slash}C-Pad64)") (class "Default")
      (node (ref "U12") (pin "64") (pinfunction "N/C_64") (pintype "passive+no_connect"))
    )
    (net (code "97") (name "unconnected-(U12-N{slash}C-Pad65)") (class "Default")
      (node (ref "U12") (pin "65") (pinfunction "N/C_65") (pintype "passive+no_connect"))
    )
    (net (code "98") (name "unconnected-(U12-N{slash}C-Pad67)") (class "Default")
      (node (ref "U12") (pin "67") (pinfunction "N/C_67") (pintype "passive+no_connect"))
    )
    (net (code "99") (name "unconnected-(U12-PERn0-Pad39)") (class "Default")
      (node (ref "U12") (pin "39") (pinfunction "PERn0_39") (pintype "passive"))
    )
    (net (code "100") (name "unconnected-(U12-PERp0-Pad40)") (class "Default")
      (node (ref "U12") (pin "40") (pinfunction "PERp0_40") (pintype "passive"))
    )
    (net (code "101") (name "unconnected-(U12-PETn0-Pad36)") (class "Default")
      (node (ref "U12") (pin "36") (pinfunction "PETn0_36") (pintype "passive"))
    )
    (net (code "102") (name "unconnected-(U12-PETp0-Pad37)") (class "Default")
      (node (ref "U12") (pin "37") (pinfunction "PETp0_37") (pintype "passive"))
    )
    (net (code "103") (name "unconnected-(U12-REFCLKn0-Pad33)") (class "Default")
      (node (ref "U12") (pin "33") (pinfunction "REFCLKn0_33") (pintype "passive"))
    )
    (net (code "104") (name "unconnected-(U12-REFCLKp0-Pad34)") (class "Default")
      (node (ref "U12") (pin "34") (pinfunction "REFCLKp0_34") (pintype "passive"))
    )
  )
)
